# 10-multimodal-combined-sensor.net
KiCad netlist of a schematic drawn in Altium Designer
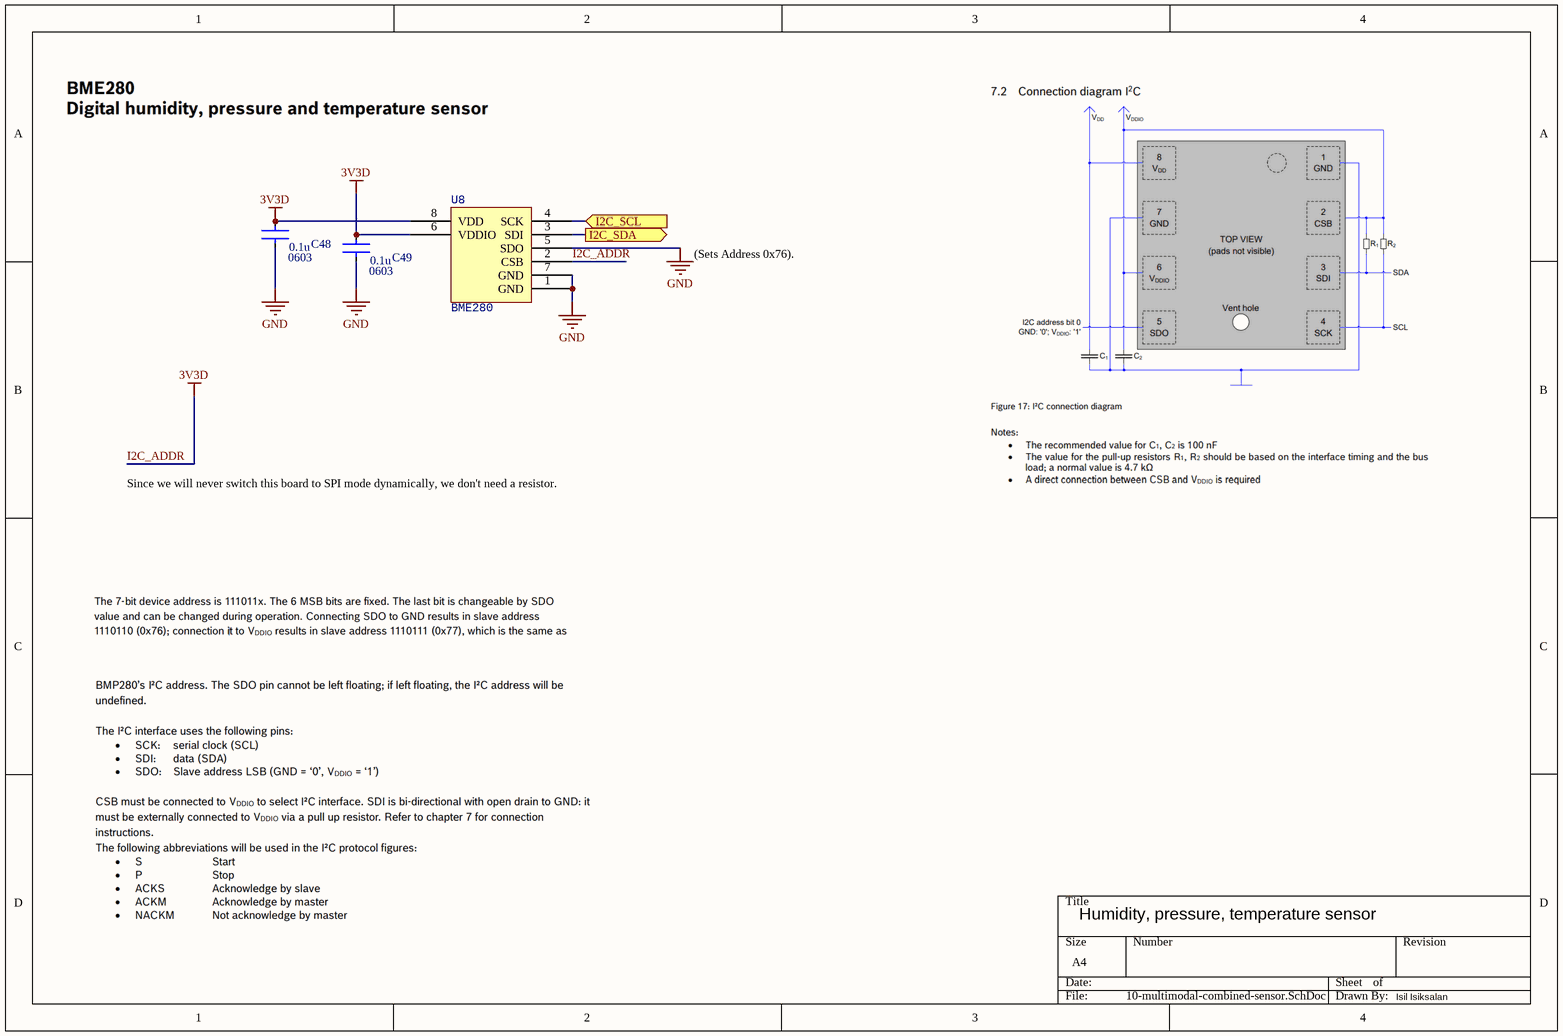
[diagram p0: 10-multimodal-combined-sensor.SchDoc]

(export (version "E")
  (design (tool "Eeschema 10.0.6"))
  (components
    (comp (ref "C48")
      (value "CGA3E2X7R1H104K080AA")
      (footprint "CAPTDK0603")
      (description "CAP CER 0.1UF 50V X7R 0603")
      (libsource (lib "multimodal") (part "CGA3E2X7R1H104K080AA"))
    )
    (comp (ref "C49")
      (value "CGA3E2X7R1H104K080AA")
      (footprint "CAPTDK0603")
      (description "CAP CER 0.1UF 50V X7R 0603")
      (libsource (lib "multimodal") (part "CGA3E2X7R1H104K080AA"))
    )
    (comp (ref "U8") (value "BME280") (footprint "BME280") (libsource (lib "multimodal") (part "BME280")))
  )
  (nets
    (net (code "1") (name "/I2C_SCL") (class "Default")
      (node (ref "U8") (pin "4") (pinfunction "SCK_4") (pintype "passive"))
    )
    (net (code "2") (name "/I2C_SDA") (class "Default")
      (node (ref "U8") (pin "3") (pinfunction "SDI_3") (pintype "passive"))
    )
    (net (code "3") (name "3V3D") (class "Default")
      (node (ref "C48") (pin "1") (pinfunction "1_1") (pintype "passive"))
      (node (ref "C49") (pin "1") (pinfunction "1_1") (pintype "passive"))
      (node (ref "U8") (pin "2") (pinfunction "CSB_2") (pintype "passive"))
      (node (ref "U8") (pin "6") (pinfunction "VDDIO_6") (pintype "passive"))
      (node (ref "U8") (pin "8") (pinfunction "VDD_8") (pintype "passive"))
    )
    (net (code "4") (name "GND") (class "Default")
      (node (ref "C48") (pin "2") (pinfunction "2_2") (pintype "passive"))
      (node (ref "C49") (pin "2") (pinfunction "2_2") (pintype "passive"))
      (node (ref "U8") (pin "1") (pinfunction "GND_1") (pintype "passive"))
      (node (ref "U8") (pin "5") (pinfunction "SDO_5") (pintype "passive"))
      (node (ref "U8") (pin "7") (pinfunction "GND_7") (pintype "passive"))
    )
  )
)
